# lesson_1_1.net
KiCad netlist of a schematic drawn in EasyEDA
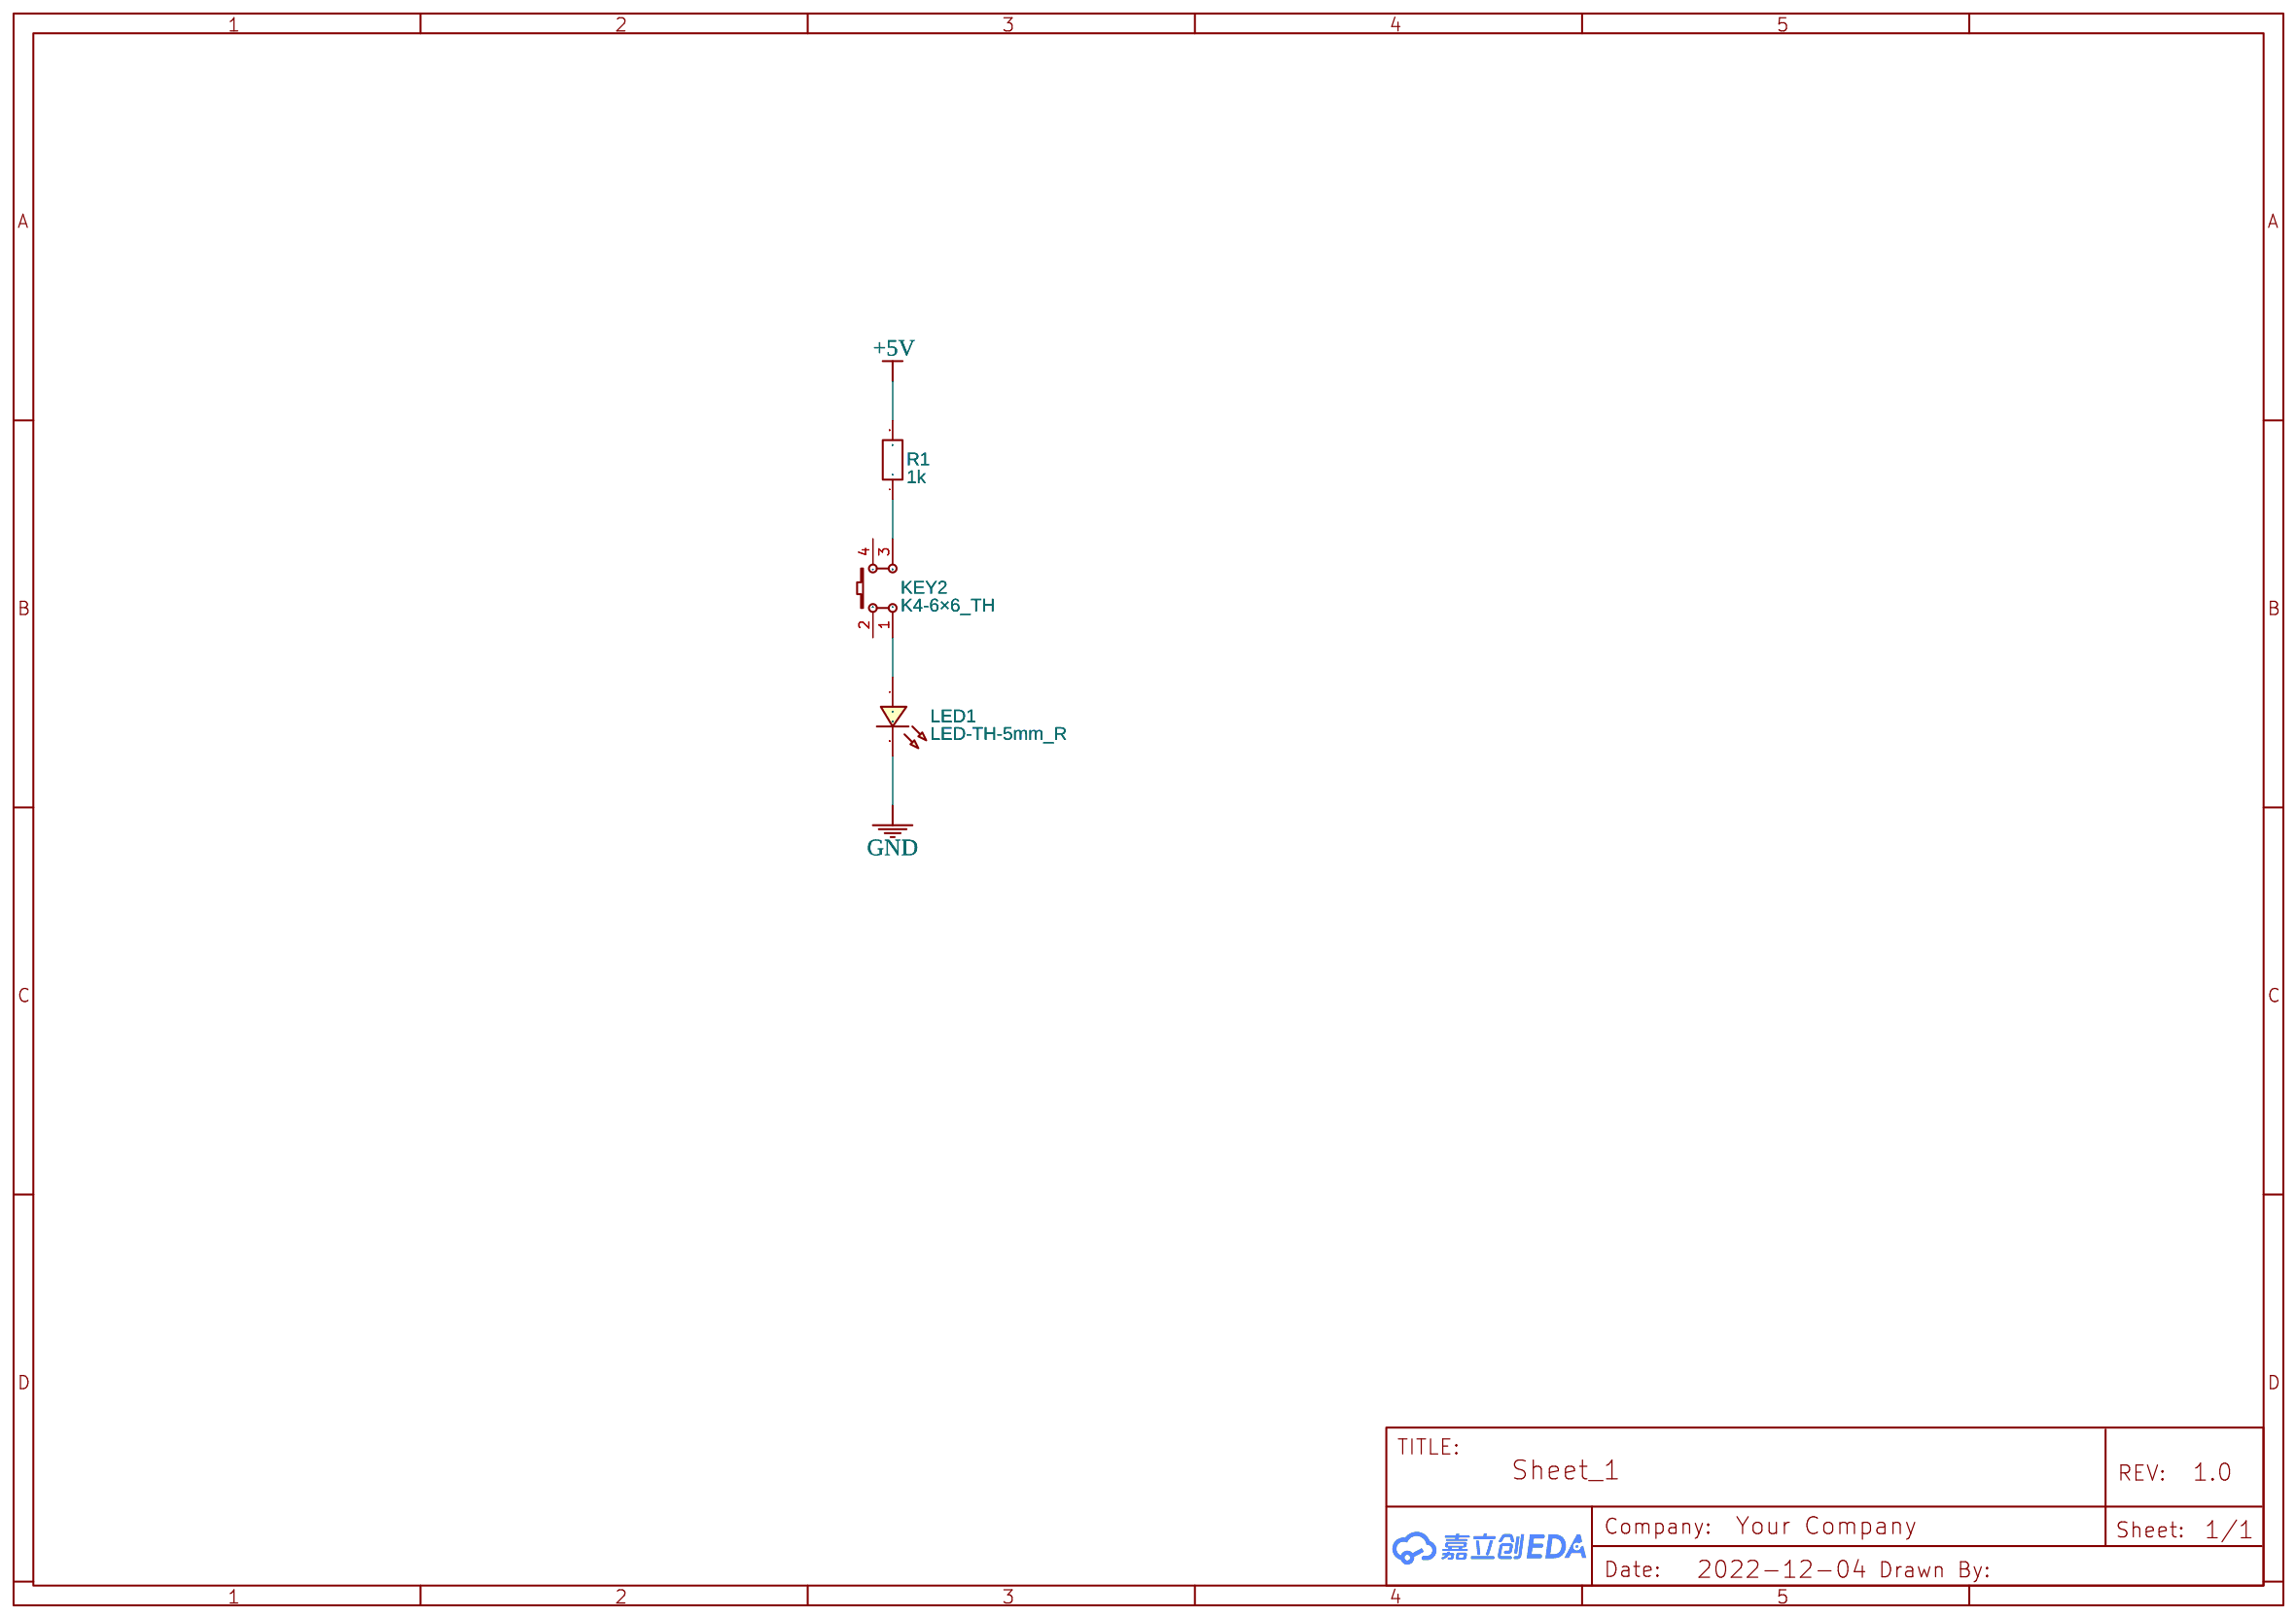
[diagram p0: schematic sheet]

(export (version "E")
  (design (tool "Eeschema 10.0.6"))
  (components
    (comp (ref "KEY2")
      (value "K4-6×6_TH")
      (fields
        (field (name "BOM_Manufacturer Part") "K2-1102DP-E4SW-04")
        (field (name "BOM_Supplier Part") "C136684")
      )
      (libsource (lib "") (part "K4-6×6_TH"))
    )
    (comp (ref "LED1")
      (value "LED-TH-5mm_R")
      (fields
        (field (name "BOM_Manufacturer Part") "333-2SURD/S530-A3")
        (field (name "BOM_Supplier Part") "C87271")
      )
      (libsource (lib "") (part "LED-TH-5mm_R"))
    )
    (comp (ref "R1") (value "1k") (libsource (lib "") (part "R_AXIAL-1.0_EU")))
  )
  (nets
    (net (code "1") (name "+5V") (class "Default")
      (node (ref "R1") (pin "2") (pinfunction "2_2") (pintype "unspecified"))
    )
    (net (code "2") (name "GND") (class "Default")
      (node (ref "LED1") (pin "2") (pinfunction "2_2") (pintype "unspecified"))
    )
    (net (code "3") (name "Net-(KEY2-Pad1)") (class "Default")
      (node (ref "KEY2") (pin "1") (pinfunction "1_1") (pintype "unspecified"))
      (node (ref "LED1") (pin "1") (pinfunction "1_1") (pintype "unspecified"))
    )
    (net (code "4") (name "Net-(KEY2-Pad3)") (class "Default")
      (node (ref "KEY2") (pin "3") (pinfunction "3_3") (pintype "unspecified"))
      (node (ref "R1") (pin "1") (pinfunction "1_1") (pintype "unspecified"))
    )
    (net (code "5") (name "unconnected-(KEY2-Pad2)") (class "Default")
      (node (ref "KEY2") (pin "2") (pinfunction "2_2") (pintype "unspecified"))
    )
    (net (code "6") (name "unconnected-(KEY2-Pad4)") (class "Default")
      (node (ref "KEY2") (pin "4") (pinfunction "4_4") (pintype "unspecified"))
    )
  )
)
